# PCB_PDB.net
KiCad netlist of a schematic drawn in Altium Designer
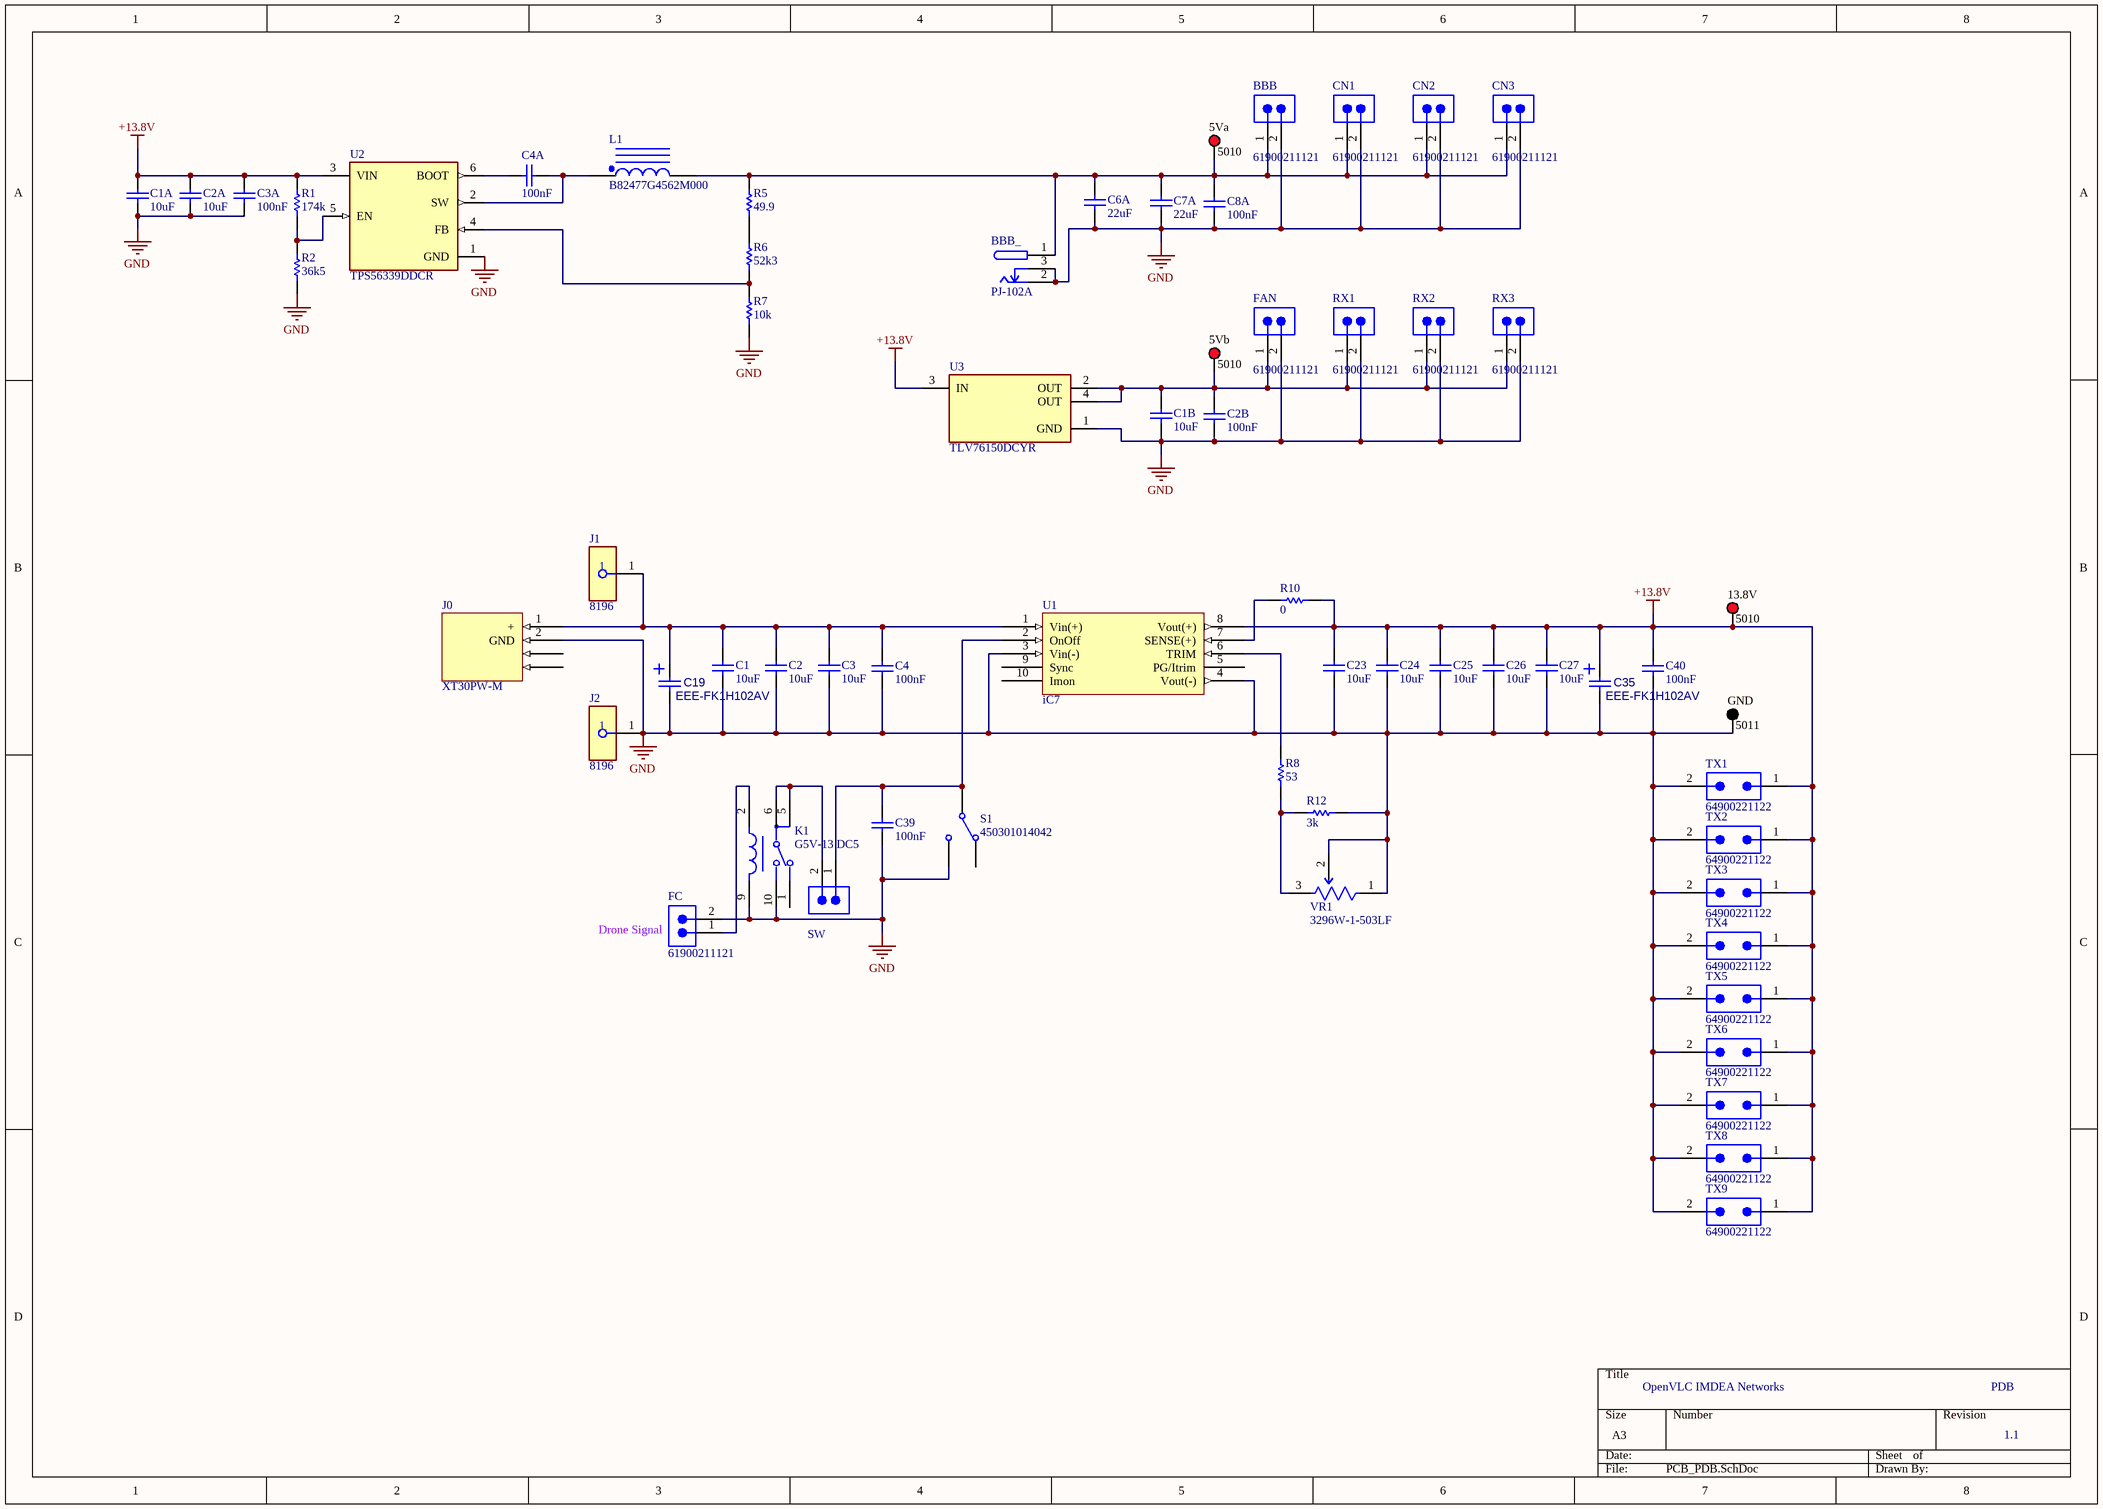
[diagram p0: PCB_PDB.SchDoc]

(export (version "E")
  (design (tool "Eeschema 10.0.6"))
  (components
    (comp (ref "5Va")
      (value "5010")
      (footprint "KSTN-5010_V")
      (description "Test Point, Red, Through Hole, RoHS, Bulk")
      (fields (field (name "MANUFACTURER") "Keystone"))
      (libsource (lib "Altium Content Vault") (part "TESTPOINT_RED"))
    )
    (comp (ref "5Vb")
      (value "5010")
      (footprint "KSTN-5010_V")
      (description "Test Point, Red, Through Hole, RoHS, Bulk")
      (fields (field (name "MANUFACTURER") "Keystone"))
      (libsource (lib "Altium Content Vault") (part "TESTPOINT_RED"))
    )
    (comp (ref "13.8V")
      (value "5010")
      (footprint "KSTN-5010_V")
      (description "Test Point, Red, Through Hole, RoHS, Bulk")
      (fields (field (name "MANUFACTURER") "Keystone"))
      (libsource (lib "Altium Content Vault") (part "TESTPOINT_RED"))
    )
    (comp (ref "BBB")
      (value "61900211121")
      (footprint "61900211121")
      (libsource (lib "Altium Content Vault") (part "Header_Male_1R_02P"))
    )
    (comp (ref "BBB_")
      (value "PJ-102A")
      (footprint "FP-PJ-102A-MFG")
      (description "PJ-102A 2.0 x 6.5 mm, 2.5 A, Horizontal, Through Hole, Tapered Pins, Dc Power Jack Connector")
      (libsource (lib "Altium Content Vault") (part "c639f672d24b5d70918fa8d934b95d1"))
    )
    (comp (ref "C1")
      (value "10uF")
      (footprint "RESC1608X55N")
      (description "Capacitor")
      (fields (field (name "Comment") "GRM188R6YA106MA73D") (field (name "PUBLISHER") "Altium Limited"))
      (libsource (lib "Miscellaneous Devices") (part "Cap"))
    )
    (comp (ref "C1A")
      (value "10uF")
      (footprint "RESC1608X55N")
      (description "Capacitor")
      (fields (field (name "Comment") "GRM188R6YA106MA73D") (field (name "PUBLISHER") "Altium Limited"))
      (libsource (lib "Miscellaneous Devices") (part "Cap"))
    )
    (comp (ref "C1B")
      (value "10uF")
      (footprint "RESC1608X55N")
      (description "Capacitor")
      (fields (field (name "Comment") "GRM188R6YA106MA73D") (field (name "PUBLISHER") "Altium Limited"))
      (libsource (lib "Miscellaneous Devices") (part "Cap"))
    )
    (comp (ref "C2")
      (value "10uF")
      (footprint "RESC1608X55N")
      (description "Capacitor")
      (fields (field (name "Comment") "GRM188R6YA106MA73D") (field (name "PUBLISHER") "Altium Limited"))
      (libsource (lib "Miscellaneous Devices") (part "Cap"))
    )
    (comp (ref "C2A")
      (value "10uF")
      (footprint "RESC1608X55N")
      (description "Capacitor")
      (fields (field (name "Comment") "GRM188R6YA106MA73D") (field (name "PUBLISHER") "Altium Limited"))
      (libsource (lib "Miscellaneous Devices") (part "Cap"))
    )
    (comp (ref "C2B")
      (value "100nF")
      (footprint "RESC1608X55N")
      (description "Capacitor")
      (fields (field (name "Comment") "GCM188R71H104KA57J") (field (name "PUBLISHER") "Altium Limited"))
      (libsource (lib "Miscellaneous Devices") (part "Cap"))
    )
    (comp (ref "C3")
      (value "10uF")
      (footprint "RESC1608X55N")
      (description "Capacitor")
      (fields (field (name "Comment") "GRM188R6YA106MA73D") (field (name "PUBLISHER") "Altium Limited"))
      (libsource (lib "Miscellaneous Devices") (part "Cap"))
    )
    (comp (ref "C3A")
      (value "100nF")
      (footprint "RESC1608X55N")
      (description "Capacitor")
      (fields (field (name "Comment") "GRM188R6YA106MA73D") (field (name "PUBLISHER") "Altium Limited"))
      (libsource (lib "Miscellaneous Devices") (part "Cap"))
    )
    (comp (ref "C4")
      (value "100nF")
      (footprint "RESC1608X55N")
      (description "Capacitor")
      (fields (field (name "Comment") "GCM188R71H104KA57J") (field (name "PUBLISHER") "Altium Limited"))
      (libsource (lib "Miscellaneous Devices") (part "Cap"))
    )
    (comp (ref "C4A")
      (value "100nF")
      (footprint "RESC1608X55N")
      (description "Capacitor")
      (fields (field (name "Comment") "GRM188R6YA106MA73D") (field (name "PUBLISHER") "Altium Limited"))
      (libsource (lib "Miscellaneous Devices") (part "Cap"))
    )
    (comp (ref "C6A")
      (value "22uF")
      (footprint "RESC1608X55N")
      (description "Capacitor")
      (fields (field (name "Comment") "GRM188R6YA106MA73D") (field (name "PUBLISHER") "Altium Limited"))
      (libsource (lib "Miscellaneous Devices") (part "Cap"))
    )
    (comp (ref "C7A")
      (value "22uF")
      (footprint "RESC1608X55N")
      (description "Capacitor")
      (fields (field (name "Comment") "GRM188R6YA106MA73D") (field (name "PUBLISHER") "Altium Limited"))
      (libsource (lib "Miscellaneous Devices") (part "Cap"))
    )
    (comp (ref "C8A")
      (value "100nF")
      (footprint "RESC1608X55N")
      (description "Capacitor")
      (fields (field (name "Comment") "GCM188R71H104KA57J") (field (name "PUBLISHER") "Altium Limited"))
      (libsource (lib "Miscellaneous Devices") (part "Cap"))
    )
    (comp (ref "C19")
      (value "EEE-FK1H102AV")
      (footprint "CAP-17x17")
      (description "CAP-17x17")
      (libsource (lib "Edson Santos") (part "CAP-17x17"))
    )
    (comp (ref "C23")
      (value "10uF")
      (footprint "RESC1608X55N")
      (description "Capacitor")
      (fields (field (name "Comment") "GRM188R6YA106MA73D") (field (name "PUBLISHER") "Altium Limited"))
      (libsource (lib "Miscellaneous Devices") (part "Cap"))
    )
    (comp (ref "C24")
      (value "10uF")
      (footprint "RESC1608X55N")
      (description "Capacitor")
      (fields (field (name "Comment") "GRM188R6YA106MA73D") (field (name "PUBLISHER") "Altium Limited"))
      (libsource (lib "Miscellaneous Devices") (part "Cap"))
    )
    (comp (ref "C25")
      (value "10uF")
      (footprint "RESC1608X55N")
      (description "Capacitor")
      (fields (field (name "Comment") "GRM188R6YA106MA73D") (field (name "PUBLISHER") "Altium Limited"))
      (libsource (lib "Miscellaneous Devices") (part "Cap"))
    )
    (comp (ref "C26")
      (value "10uF")
      (footprint "RESC1608X55N")
      (description "Capacitor")
      (fields (field (name "Comment") "GRM188R6YA106MA73D") (field (name "PUBLISHER") "Altium Limited"))
      (libsource (lib "Miscellaneous Devices") (part "Cap"))
    )
    (comp (ref "C27")
      (value "10uF")
      (footprint "RESC1608X55N")
      (description "Capacitor")
      (fields (field (name "Comment") "GRM188R6YA106MA73D") (field (name "PUBLISHER") "Altium Limited"))
      (libsource (lib "Miscellaneous Devices") (part "Cap"))
    )
    (comp (ref "C35")
      (value "EEE-FK1H102AV")
      (footprint "CAP-17x17")
      (description "CAP-17x17")
      (libsource (lib "Edson Santos") (part "CAP-17x17"))
    )
    (comp (ref "C39")
      (value "100nF")
      (footprint "RESC1608X55N")
      (description "Capacitor")
      (fields (field (name "Comment") "GCM188R71H104KA57J") (field (name "PUBLISHER") "Altium Limited"))
      (libsource (lib "Miscellaneous Devices") (part "Cap"))
    )
    (comp (ref "C40")
      (value "100nF")
      (footprint "RESC1608X55N")
      (description "Capacitor")
      (fields (field (name "Comment") "GCM188R71H104KA57J") (field (name "PUBLISHER") "Altium Limited"))
      (libsource (lib "Miscellaneous Devices") (part "Cap"))
    )
    (comp (ref "CN1")
      (value "61900211121")
      (footprint "61900211121")
      (libsource (lib "Altium Content Vault") (part "Header_Male_1R_02P"))
    )
    (comp (ref "CN2")
      (value "61900211121")
      (footprint "61900211121")
      (libsource (lib "Altium Content Vault") (part "Header_Male_1R_02P"))
    )
    (comp (ref "CN3")
      (value "61900211121")
      (footprint "61900211121")
      (libsource (lib "Altium Content Vault") (part "Header_Male_1R_02P"))
    )
    (comp (ref "FAN")
      (value "61900211121")
      (footprint "61900211121")
      (libsource (lib "Altium Content Vault") (part "Header_Male_1R_02P"))
    )
    (comp (ref "FC")
      (value "61900211121")
      (footprint "61900211121")
      (libsource (lib "Altium Content Vault") (part "Header_Male_1R_02P"))
    )
    (comp (ref "GND")
      (value "5011")
      (footprint "KSTN-5011_V")
      (description "Test Point, Black, Through Hole, RoHS, Bulk")
      (fields (field (name "MANUFACTURER") "Keystone"))
      (libsource (lib "Altium Content Vault") (part "TESTPOINT_BLACK"))
    )
    (comp (ref "J0")
      (value "XT30PW-M")
      (footprint "XT30-Footprint-1")
      (libsource (lib "Edson Santos") (part "XT30PW-M"))
    )
    (comp (ref "J1")
      (value "8196")
      (footprint "FP-8196-MFG")
      (description "8196 PC Screw Terminal 0.67 in. L Brass Tin Plate Stainless Steel Mounting Hole 0.045 in. T")
      (libsource (lib "Altium Content Vault") (part "98815daf2f2c152b0c43f5ab9800df6"))
    )
    (comp (ref "J2")
      (value "8196")
      (footprint "FP-8196-MFG")
      (description "8196 PC Screw Terminal 0.67 in. L Brass Tin Plate Stainless Steel Mounting Hole 0.045 in. T")
      (libsource (lib "Altium Content Vault") (part "98815daf2f2c152b0c43f5ab9800df6"))
    )
    (comp (ref "K1")
      (value "G5V-13 DC5")
      (footprint "FP-G5V-13_DC5-MFG")
      (description "RELAY GEN PURPOSE SPDT 1A 5VDC")
      (libsource (lib "Altium Content Vault") (part "f0f19af8d64f0b7d991e63e7b06891a"))
    )
    (comp (ref "L1")
      (value "B82477G4562M000")
      (footprint "EATN-DR125_V")
      (fields (field (name "MANUFACTURER") "EATON"))
      (libsource (lib "Altium Content Vault") (part "IND-DOT-2"))
    )
    (comp (ref "R1")
      (value "174k")
      (footprint "RESC1608X55N")
      (description "Resistor")
      (fields (field (name "Comment") "RN73R1JTTD53R0B25") (field (name "PUBLISHER") "Altium Limited"))
      (libsource (lib "Miscellaneous Devices") (part "Res1"))
    )
    (comp (ref "R2")
      (value "36k5")
      (footprint "RESC1608X55N")
      (description "Resistor")
      (fields (field (name "Comment") "RN73R1JTTD53R0B25") (field (name "PUBLISHER") "Altium Limited"))
      (libsource (lib "Miscellaneous Devices") (part "Res1"))
    )
    (comp (ref "R5")
      (value "49.9")
      (footprint "RESC1608X55N")
      (description "Resistor")
      (fields (field (name "Comment") "RN73R1JTTD53R0B25") (field (name "PUBLISHER") "Altium Limited"))
      (libsource (lib "Miscellaneous Devices") (part "Res1"))
    )
    (comp (ref "R6")
      (value "52k3")
      (footprint "RESC1608X55N")
      (description "Resistor")
      (fields (field (name "Comment") "RN73R1JTTD53R0B25") (field (name "PUBLISHER") "Altium Limited"))
      (libsource (lib "Miscellaneous Devices") (part "Res1"))
    )
    (comp (ref "R7")
      (value "10k")
      (footprint "RESC1608X55N")
      (description "Resistor")
      (fields (field (name "Comment") "RN73R1JTTD53R0B25") (field (name "PUBLISHER") "Altium Limited"))
      (libsource (lib "Miscellaneous Devices") (part "Res1"))
    )
    (comp (ref "R8")
      (value "53")
      (footprint "RESC1608X55N")
      (description "Resistor")
      (fields (field (name "Comment") "RN73R1JTTD53R0B25") (field (name "PUBLISHER") "Altium Limited"))
      (libsource (lib "Miscellaneous Devices") (part "Res1"))
    )
    (comp (ref "R10")
      (value "0")
      (footprint "RESC1608X55N")
      (description "Resistor")
      (fields (field (name "Comment") "RMCF0603ZT0R00") (field (name "PUBLISHER") "Altium Limited"))
      (libsource (lib "Miscellaneous Devices") (part "Res1"))
    )
    (comp (ref "R12")
      (value "3k")
      (footprint "RESC1608X55N")
      (description "Resistor")
      (fields (field (name "Comment") "RK73H1JTTD2001D") (field (name "PUBLISHER") "Altium Limited"))
      (libsource (lib "Miscellaneous Devices") (part "Res1"))
    )
    (comp (ref "RX1")
      (value "61900211121")
      (footprint "61900211121")
      (libsource (lib "Altium Content Vault") (part "Header_Male_1R_02P"))
    )
    (comp (ref "RX2")
      (value "61900211121")
      (footprint "61900211121")
      (libsource (lib "Altium Content Vault") (part "Header_Male_1R_02P"))
    )
    (comp (ref "RX3")
      (value "61900211121")
      (footprint "61900211121")
      (libsource (lib "Altium Content Vault") (part "Header_Male_1R_02P"))
    )
    (comp (ref "S1")
      (value "450301014042")
      (footprint "450301014042")
      (libsource (lib "Altium Content Vault") (part "SPDT"))
    )
    (comp (ref "SW")
      (value "61300211121")
      (footprint "61300211121")
      (libsource (lib "Altium Content Vault") (part "Header_Male_1R_02P"))
    )
    (comp (ref "TX1")
      (value "64900221122")
      (footprint "64900221122")
      (libsource (lib "Altium Content Vault") (part "Header_Male_2R_02P(A)"))
    )
    (comp (ref "TX2")
      (value "64900221122")
      (footprint "64900221122")
      (libsource (lib "Altium Content Vault") (part "Header_Male_2R_02P(A)"))
    )
    (comp (ref "TX3")
      (value "64900221122")
      (footprint "64900221122")
      (libsource (lib "Altium Content Vault") (part "Header_Male_2R_02P(A)"))
    )
    (comp (ref "TX4")
      (value "64900221122")
      (footprint "64900221122")
      (libsource (lib "Altium Content Vault") (part "Header_Male_2R_02P(A)"))
    )
    (comp (ref "TX5")
      (value "64900221122")
      (footprint "64900221122")
      (libsource (lib "Altium Content Vault") (part "Header_Male_2R_02P(A)"))
    )
    (comp (ref "TX6")
      (value "64900221122")
      (footprint "64900221122")
      (libsource (lib "Altium Content Vault") (part "Header_Male_2R_02P(A)"))
    )
    (comp (ref "TX7")
      (value "64900221122")
      (footprint "64900221122")
      (libsource (lib "Altium Content Vault") (part "Header_Male_2R_02P(A)"))
    )
    (comp (ref "TX8")
      (value "64900221122")
      (footprint "64900221122")
      (libsource (lib "Altium Content Vault") (part "Header_Male_2R_02P(A)"))
    )
    (comp (ref "TX9")
      (value "64900221122")
      (footprint "64900221122")
      (libsource (lib "Altium Content Vault") (part "Header_Male_2R_02P(A)"))
    )
    (comp (ref "U1")
      (value "iC7")
      (footprint "New footprint 1")
      (libsource (lib "Edson Santos") (part "i7C"))
    )
    (comp (ref "U2")
      (value "TPS56339DDCR")
      (footprint "FP-DDC0006A-MFG")
      (description "PWR MGMT SPECIALIZED REGULATOR")
      (fields
        (field (name "MANUFACTURER") "Texas Instruments")
        (field (name "OCTOPART") "https://octopart.com/tps56339ddcr-texas+instruments-101466410")
      )
      (libsource (lib "Altium Content Vault") (part "2ef13c8a92b2ccd2de8c1984d71b5d5"))
    )
    (comp (ref "U3")
      (value "TLV76150DCYR")
      (footprint "FP-DCY0004A-MFG")
      (description "TLV76150DCYR 1-A 16-V high-PSRR linear voltage regulator 4-SOT-223 -40 to 125")
      (libsource (lib "Altium Content Vault") (part "991ffb903c51cf6179ce9942c0606aa"))
    )
    (comp (ref "VR1")
      (value "3296W-1-503LF")
      (footprint "FP-3296W-MFG")
      (description "TRIMMER 50K OHM 0.5W PC PIN TOP")
      (fields (field (name "TOLERANCE") "10%"))
      (libsource (lib "Altium Content Vault") (part "2dcfd2547301a7d3209a5e99acfd772"))
    )
  )
  (nets
    (net (code "1") (name "+13.8V") (class "Default")
      (node (ref "13.8V") (pin "1") (pinfunction "1_1") (pintype "passive"))
      (node (ref "C1A") (pin "2") (pinfunction "2_2") (pintype "passive"))
      (node (ref "C23") (pin "2") (pinfunction "2_2") (pintype "passive"))
      (node (ref "C24") (pin "2") (pinfunction "2_2") (pintype "passive"))
      (node (ref "C25") (pin "2") (pinfunction "2_2") (pintype "passive"))
      (node (ref "C26") (pin "2") (pinfunction "2_2") (pintype "passive"))
      (node (ref "C27") (pin "2") (pinfunction "2_2") (pintype "passive"))
      (node (ref "C2A") (pin "2") (pinfunction "2_2") (pintype "passive"))
      (node (ref "C35") (pin "1") (pinfunction "1_1") (pintype "passive"))
      (node (ref "C3A") (pin "2") (pinfunction "2_2") (pintype "passive"))
      (node (ref "C40") (pin "2") (pinfunction "2_2") (pintype "passive"))
      (node (ref "R1") (pin "1") (pinfunction "1_1") (pintype "passive"))
      (node (ref "R10") (pin "1") (pinfunction "1_1") (pintype "passive"))
      (node (ref "TX1") (pin "1") (pinfunction "1_1") (pintype "passive"))
      (node (ref "TX2") (pin "1") (pinfunction "1_1") (pintype "passive"))
      (node (ref "TX3") (pin "1") (pinfunction "1_1") (pintype "passive"))
      (node (ref "TX4") (pin "1") (pinfunction "1_1") (pintype "passive"))
      (node (ref "TX5") (pin "1") (pinfunction "1_1") (pintype "passive"))
      (node (ref "TX6") (pin "1") (pinfunction "1_1") (pintype "passive"))
      (node (ref "TX7") (pin "1") (pinfunction "1_1") (pintype "passive"))
      (node (ref "TX8") (pin "1") (pinfunction "1_1") (pintype "passive"))
      (node (ref "TX9") (pin "1") (pinfunction "1_1") (pintype "passive"))
      (node (ref "U1") (pin "8") (pinfunction "Vout(+)_8") (pintype "output"))
      (node (ref "U2") (pin "3") (pinfunction "VIN_3") (pintype "power_in"))
      (node (ref "U3") (pin "3") (pinfunction "IN_3") (pintype "power_in"))
    )
    (net (code "2") (name "GND") (class "Default")
      (node (ref "BBB") (pin "2") (pinfunction "2_2") (pintype "passive"))
      (node (ref "BBB_") (pin "2") (pinfunction "2_2") (pintype "passive"))
      (node (ref "BBB_") (pin "3") (pinfunction "3_3") (pintype "passive"))
      (node (ref "C1") (pin "1") (pinfunction "1_1") (pintype "passive"))
      (node (ref "C19") (pin "2") (pinfunction "2_2") (pintype "passive"))
      (node (ref "C1A") (pin "1") (pinfunction "1_1") (pintype "passive"))
      (node (ref "C1B") (pin "1") (pinfunction "1_1") (pintype "passive"))
      (node (ref "C2") (pin "1") (pinfunction "1_1") (pintype "passive"))
      (node (ref "C23") (pin "1") (pinfunction "1_1") (pintype "passive"))
      (node (ref "C24") (pin "1") (pinfunction "1_1") (pintype "passive"))
      (node (ref "C25") (pin "1") (pinfunction "1_1") (pintype "passive"))
      (node (ref "C26") (pin "1") (pinfunction "1_1") (pintype "passive"))
      (node (ref "C27") (pin "1") (pinfunction "1_1") (pintype "passive"))
      (node (ref "C2A") (pin "1") (pinfunction "1_1") (pintype "passive"))
      (node (ref "C2B") (pin "2") (pinfunction "2_2") (pintype "passive"))
      (node (ref "C3") (pin "1") (pinfunction "1_1") (pintype "passive"))
      (node (ref "C35") (pin "2") (pinfunction "2_2") (pintype "passive"))
      (node (ref "C39") (pin "2") (pinfunction "2_2") (pintype "passive"))
      (node (ref "C3A") (pin "1") (pinfunction "1_1") (pintype "passive"))
      (node (ref "C4") (pin "2") (pinfunction "2_2") (pintype "passive"))
      (node (ref "C40") (pin "1") (pinfunction "1_1") (pintype "passive"))
      (node (ref "C6A") (pin "1") (pinfunction "1_1") (pintype "passive"))
      (node (ref "C7A") (pin "1") (pinfunction "1_1") (pintype "passive"))
      (node (ref "C8A") (pin "2") (pinfunction "2_2") (pintype "passive"))
      (node (ref "CN1") (pin "2") (pinfunction "2_2") (pintype "passive"))
      (node (ref "CN2") (pin "2") (pinfunction "2_2") (pintype "passive"))
      (node (ref "CN3") (pin "2") (pinfunction "2_2") (pintype "passive"))
      (node (ref "FAN") (pin "2") (pinfunction "2_2") (pintype "passive"))
      (node (ref "FC") (pin "2") (pinfunction "2_2") (pintype "passive"))
      (node (ref "GND") (pin "1") (pinfunction "1_1") (pintype "passive"))
      (node (ref "J0") (pin "2") (pinfunction "GND_2") (pintype "input"))
      (node (ref "J2") (pin "1") (pinfunction "1_1") (pintype "passive"))
      (node (ref "K1") (pin "10") (pinfunction "10_10") (pintype "passive"))
      (node (ref "K1") (pin "9") (pinfunction "9_9") (pintype "passive"))
      (node (ref "R12") (pin "1") (pinfunction "1_1") (pintype "passive"))
      (node (ref "R2") (pin "2") (pinfunction "2_2") (pintype "passive"))
      (node (ref "R7") (pin "2") (pinfunction "2_2") (pintype "passive"))
      (node (ref "RX1") (pin "2") (pinfunction "2_2") (pintype "passive"))
      (node (ref "RX2") (pin "2") (pinfunction "2_2") (pintype "passive"))
      (node (ref "RX3") (pin "2") (pinfunction "2_2") (pintype "passive"))
      (node (ref "S1") (pin "L2") (pinfunction "L2_L2") (pintype "passive"))
      (node (ref "TX1") (pin "2") (pinfunction "2_2") (pintype "passive"))
      (node (ref "TX2") (pin "2") (pinfunction "2_2") (pintype "passive"))
      (node (ref "TX3") (pin "2") (pinfunction "2_2") (pintype "passive"))
      (node (ref "TX4") (pin "2") (pinfunction "2_2") (pintype "passive"))
      (node (ref "TX5") (pin "2") (pinfunction "2_2") (pintype "passive"))
      (node (ref "TX6") (pin "2") (pinfunction "2_2") (pintype "passive"))
      (node (ref "TX7") (pin "2") (pinfunction "2_2") (pintype "passive"))
      (node (ref "TX8") (pin "2") (pinfunction "2_2") (pintype "passive"))
      (node (ref "TX9") (pin "2") (pinfunction "2_2") (pintype "passive"))
      (node (ref "U1") (pin "3") (pinfunction "Vin(-)_3") (pintype "input"))
      (node (ref "U1") (pin "4") (pinfunction "Vout(-)_4") (pintype "output"))
      (node (ref "U2") (pin "1") (pinfunction "GND_1") (pintype "power_in"))
      (node (ref "U3") (pin "1") (pinfunction "GND_1") (pintype "power_in"))
      (node (ref "VR1") (pin "1") (pinfunction "CCW_1") (pintype "passive"))
      (node (ref "VR1") (pin "2") (pinfunction "WIPER_2") (pintype "passive"))
    )
    (net (code "3") (name "Net-(5Va-Pad1)") (class "Default")
      (node (ref "5Va") (pin "1") (pinfunction "1_1") (pintype "passive"))
      (node (ref "BBB") (pin "1") (pinfunction "1_1") (pintype "passive"))
      (node (ref "BBB_") (pin "1") (pinfunction "1_1") (pintype "passive"))
      (node (ref "C6A") (pin "2") (pinfunction "2_2") (pintype "passive"))
      (node (ref "C7A") (pin "2") (pinfunction "2_2") (pintype "passive"))
      (node (ref "C8A") (pin "1") (pinfunction "1_1") (pintype "passive"))
      (node (ref "CN1") (pin "1") (pinfunction "1_1") (pintype "passive"))
      (node (ref "CN2") (pin "1") (pinfunction "1_1") (pintype "passive"))
      (node (ref "CN3") (pin "1") (pinfunction "1_1") (pintype "passive"))
      (node (ref "L1") (pin "2") (pinfunction "2_2") (pintype "passive"))
      (node (ref "R5") (pin "1") (pinfunction "1_1") (pintype "passive"))
    )
    (net (code "4") (name "Net-(5Vb-Pad1)") (class "Default")
      (node (ref "5Vb") (pin "1") (pinfunction "1_1") (pintype "passive"))
      (node (ref "C1B") (pin "2") (pinfunction "2_2") (pintype "passive"))
      (node (ref "C2B") (pin "1") (pinfunction "1_1") (pintype "passive"))
      (node (ref "FAN") (pin "1") (pinfunction "1_1") (pintype "passive"))
      (node (ref "RX1") (pin "1") (pinfunction "1_1") (pintype "passive"))
      (node (ref "RX2") (pin "1") (pinfunction "1_1") (pintype "passive"))
      (node (ref "RX3") (pin "1") (pinfunction "1_1") (pintype "passive"))
      (node (ref "U3") (pin "2") (pinfunction "OUT_2") (pintype "passive"))
      (node (ref "U3") (pin "4") (pinfunction "OUT_4") (pintype "passive"))
    )
    (net (code "5") (name "Net-(FC-Pad1)") (class "Default")
      (node (ref "FC") (pin "1") (pinfunction "1_1") (pintype "passive"))
      (node (ref "K1") (pin "2") (pinfunction "2_2") (pintype "passive"))
    )
    (net (code "6") (name "Net-(J0-+)") (class "Default")
      (node (ref "C1") (pin "2") (pinfunction "2_2") (pintype "passive"))
      (node (ref "C19") (pin "1") (pinfunction "1_1") (pintype "passive"))
      (node (ref "C2") (pin "2") (pinfunction "2_2") (pintype "passive"))
      (node (ref "C3") (pin "2") (pinfunction "2_2") (pintype "passive"))
      (node (ref "C4") (pin "1") (pinfunction "1_1") (pintype "passive"))
      (node (ref "J0") (pin "1") (pinfunction "+_1") (pintype "input"))
      (node (ref "J1") (pin "1") (pinfunction "1_1") (pintype "passive"))
      (node (ref "U1") (pin "1") (pinfunction "Vin(+)_1") (pintype "input"))
    )
    (net (code "7") (name "Net-(K1-Pad5)") (class "Default")
      (node (ref "K1") (pin "5") (pinfunction "5_5") (pintype "passive"))
      (node (ref "K1") (pin "6") (pinfunction "6_6") (pintype "passive"))
      (node (ref "SW") (pin "2") (pinfunction "2_2") (pintype "passive"))
    )
    (net (code "8") (name "Net-(R5-Pad2)") (class "Default")
      (node (ref "R5") (pin "2") (pinfunction "2_2") (pintype "passive"))
      (node (ref "R6") (pin "1") (pinfunction "1_1") (pintype "passive"))
    )
    (net (code "9") (name "Net-(U1-OnOff)") (class "Default")
      (node (ref "C39") (pin "1") (pinfunction "1_1") (pintype "passive"))
      (node (ref "S1") (pin "COM") (pinfunction "COM_COM") (pintype "passive"))
      (node (ref "SW") (pin "1") (pinfunction "1_1") (pintype "passive"))
      (node (ref "U1") (pin "2") (pinfunction "OnOff_2") (pintype "input"))
    )
    (net (code "10") (name "Net-(U1-SENSE(+))") (class "Default")
      (node (ref "R10") (pin "2") (pinfunction "2_2") (pintype "passive"))
      (node (ref "U1") (pin "7") (pinfunction "SENSE(+)_7") (pintype "input"))
    )
    (net (code "11") (name "Net-(U1-TRIM)") (class "Default")
      (node (ref "R8") (pin "1") (pinfunction "1_1") (pintype "passive"))
      (node (ref "U1") (pin "6") (pinfunction "TRIM_6") (pintype "input"))
    )
    (net (code "12") (name "Net-(U2-BOOT)") (class "Default")
      (node (ref "C4A") (pin "2") (pinfunction "2_2") (pintype "passive"))
      (node (ref "U2") (pin "6") (pinfunction "BOOT_6") (pintype "output"))
    )
    (net (code "13") (name "Net-(U2-EN)") (class "Default")
      (node (ref "R1") (pin "2") (pinfunction "2_2") (pintype "passive"))
      (node (ref "R2") (pin "1") (pinfunction "1_1") (pintype "passive"))
      (node (ref "U2") (pin "5") (pinfunction "EN_5") (pintype "input"))
    )
    (net (code "14") (name "Net-(U2-FB)") (class "Default")
      (node (ref "R6") (pin "2") (pinfunction "2_2") (pintype "passive"))
      (node (ref "R7") (pin "1") (pinfunction "1_1") (pintype "passive"))
      (node (ref "U2") (pin "4") (pinfunction "FB_4") (pintype "input"))
    )
    (net (code "15") (name "Net-(U2-SW)") (class "Default")
      (node (ref "C4A") (pin "1") (pinfunction "1_1") (pintype "passive"))
      (node (ref "L1") (pin "1") (pinfunction "1_1") (pintype "passive"))
      (node (ref "U2") (pin "2") (pinfunction "SW_2") (pintype "output"))
    )
    (net (code "16") (name "Net-(VR1-CW)") (class "Default")
      (node (ref "R12") (pin "2") (pinfunction "2_2") (pintype "passive"))
      (node (ref "R8") (pin "2") (pinfunction "2_2") (pintype "passive"))
      (node (ref "VR1") (pin "3") (pinfunction "CW_3") (pintype "passive"))
    )
    (net (code "17") (name "unconnected-(J0-NC3-Pad3)") (class "Default")
      (node (ref "J0") (pin "3") (pinfunction "NC3_3") (pintype "input"))
    )
    (net (code "18") (name "unconnected-(J0-NC4-Pad4)") (class "Default")
      (node (ref "J0") (pin "4") (pinfunction "NC4_4") (pintype "input"))
    )
    (net (code "19") (name "unconnected-(K1-Pad1)") (class "Default")
      (node (ref "K1") (pin "1") (pinfunction "1_1") (pintype "passive"))
    )
    (net (code "20") (name "unconnected-(S1-PadL1)") (class "Default")
      (node (ref "S1") (pin "L1") (pinfunction "L1_L1") (pintype "passive"))
    )
    (net (code "21") (name "unconnected-(U1-Imon-Pad10)") (class "Default")
      (node (ref "U1") (pin "10") (pinfunction "Imon_10") (pintype "open_collector"))
    )
    (net (code "22") (name "unconnected-(U1-PG{slash}Itrim-Pad5)") (class "Default")
      (node (ref "U1") (pin "5") (pinfunction "PG/Itrim_5") (pintype "open_collector"))
    )
    (net (code "23") (name "unconnected-(U1-Sync-Pad9)") (class "Default")
      (node (ref "U1") (pin "9") (pinfunction "Sync_9") (pintype "open_collector"))
    )
  )
)
